# ext_esp32_M.net
KiCad netlist of a schematic drawn in EAGLE
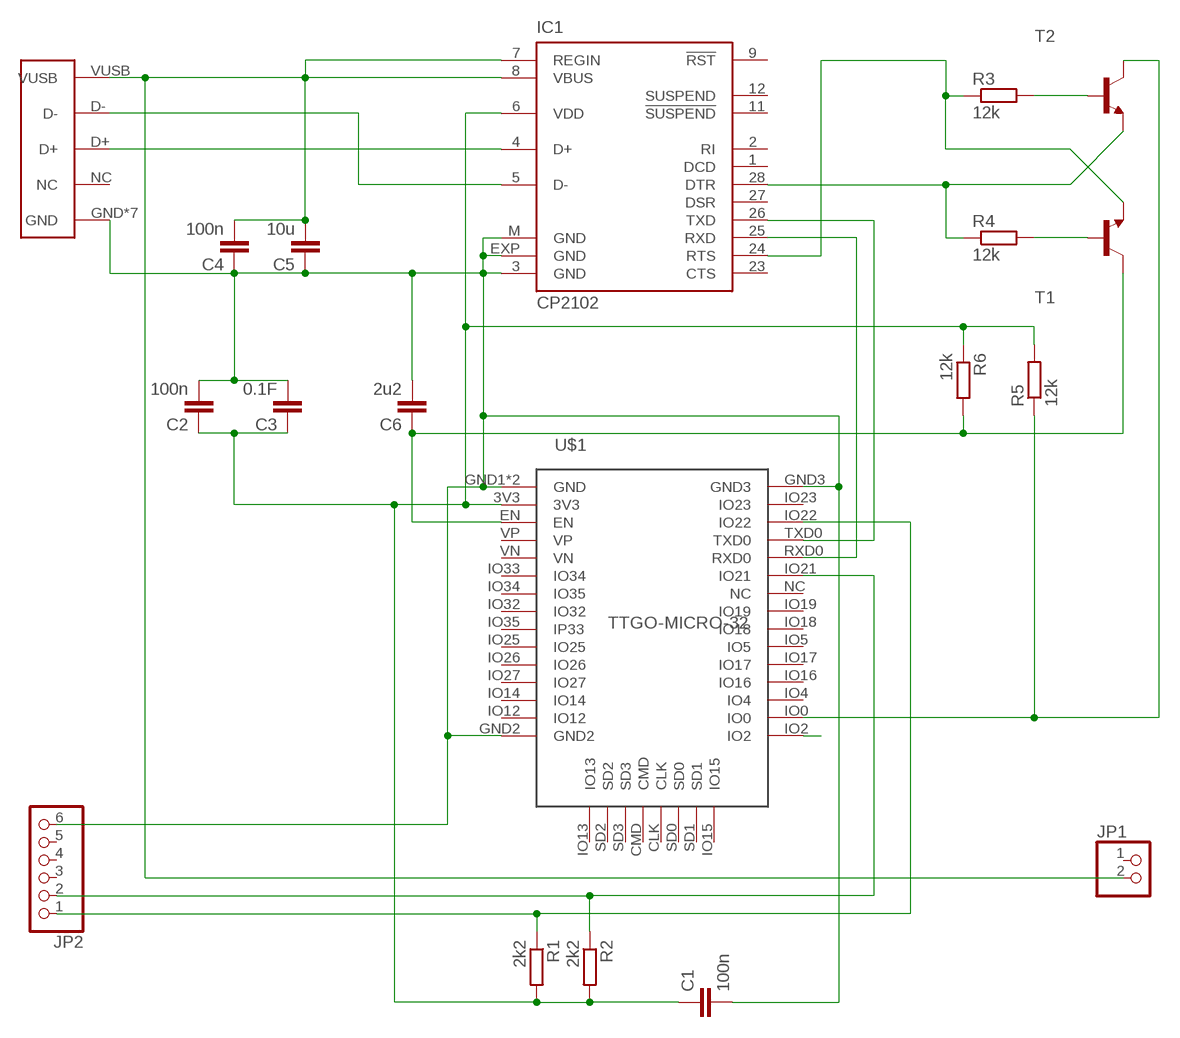
[diagram p0: schematic, sheet 1]

(export (version "E")
  (design (tool "Eeschema 10.0.6"))
  (components
    (comp (ref "C1")
      (value "100n")
      (footprint "eagle-import:C0603")
      (libsource (lib "eagle-import") (part "C-EUC0603"))
    )
    (comp (ref "C2")
      (value "100n")
      (footprint "eagle-import:C0603")
      (libsource (lib "eagle-import") (part "C-EUC0603"))
    )
    (comp (ref "C3")
      (value "0.1F")
      (footprint "eagle-import:C0603")
      (libsource (lib "eagle-import") (part "C-EUC0603"))
    )
    (comp (ref "C4")
      (value "100n")
      (footprint "eagle-import:C0603")
      (libsource (lib "eagle-import") (part "C-EUC0603"))
    )
    (comp (ref "C5")
      (value "10u")
      (footprint "eagle-import:C0603")
      (libsource (lib "eagle-import") (part "C-EUC0603"))
    )
    (comp (ref "C6")
      (value "2u2")
      (footprint "eagle-import:C0603")
      (libsource (lib "eagle-import") (part "C-EUC0603"))
    )
    (comp (ref "IC1")
      (value "CP2102")
      (footprint "eagle-import:MLP28")
      (fields (field (name "MF") "FARNELL") (field (name "MPN") "CP2102-GM"))
      (libsource (lib "eagle-import") (part "CP2102"))
    )
    (comp (ref "JP1")
      (value "PINHD-1X2")
      (footprint "eagle-import:1X02")
      (libsource (lib "eagle-import") (part "PINHD-1X2"))
    )
    (comp (ref "JP2")
      (value "PINHD-1X6")
      (footprint "eagle-import:1X06")
      (libsource (lib "eagle-import") (part "PINHD-1X6"))
    )
    (comp (ref "R1")
      (value "2k2")
      (footprint "eagle-import:R0603")
      (libsource (lib "eagle-import") (part "R-EU_R0603"))
    )
    (comp (ref "R2")
      (value "2k2")
      (footprint "eagle-import:R0603")
      (libsource (lib "eagle-import") (part "R-EU_R0603"))
    )
    (comp (ref "R3")
      (value "12k")
      (footprint "eagle-import:R0603")
      (libsource (lib "eagle-import") (part "R-EU_R0603"))
    )
    (comp (ref "R4")
      (value "12k")
      (footprint "eagle-import:R0603")
      (libsource (lib "eagle-import") (part "R-EU_R0603"))
    )
    (comp (ref "R5")
      (value "12k")
      (footprint "eagle-import:R0603")
      (libsource (lib "eagle-import") (part "R-EU_R0603"))
    )
    (comp (ref "R6")
      (value "12k")
      (footprint "eagle-import:R0603")
      (libsource (lib "eagle-import") (part "R-EU_R0603"))
    )
    (comp (ref "T1")
      (value "BC808-NPN-SOT23-BEC")
      (footprint "eagle-import:SOT23-BEC")
      (libsource (lib "eagle-import") (part "-NPN-SOT23-BECBC808"))
    )
    (comp (ref "T2")
      (value "BC808-NPN-SOT23-BEC")
      (footprint "eagle-import:SOT23-BEC")
      (libsource (lib "eagle-import") (part "-NPN-SOT23-BECBC808"))
    )
    (comp (ref "U$1")
      (value "TTGO-MICRO-32")
      (footprint "eagle-import:TTGO-MICRO-32")
      (libsource (lib "eagle-import") (part "TTGO-MICRO-32"))
    )
    (comp (ref "USB")
      (value "MICRO-USB")
      (footprint "eagle-import:MICRO-USB")
      (libsource (lib "eagle-import") (part "MICRO-USB"))
    )
  )
  (nets
    (net (code "1") (name "Net-(C1-Pad2)") (class "Default")
      (node (ref "C1") (pin "2") (pinfunction "2_2") (pintype "passive"))
      (node (ref "C2") (pin "2") (pinfunction "2_2") (pintype "passive"))
      (node (ref "C3") (pin "2") (pinfunction "2_2") (pintype "passive"))
      (node (ref "C4") (pin "1") (pinfunction "1_1") (pintype "passive"))
      (node (ref "C5") (pin "1") (pinfunction "1_1") (pintype "passive"))
      (node (ref "C6") (pin "2") (pinfunction "2_2") (pintype "passive"))
      (node (ref "IC1") (pin "3") (pinfunction "GND_3") (pintype "power_in"))
      (node (ref "IC1") (pin "EXP") (pinfunction "GND_EXP") (pintype "power_in"))
      (node (ref "IC1") (pin "M") (pinfunction "GND_M") (pintype "power_in"))
      (node (ref "JP2") (pin "6") (pinfunction "6_6") (pintype "passive"))
      (node (ref "U$1") (pin "GND1") (pinfunction "GND_GND1") (pintype "power_in"))
      (node (ref "U$1") (pin "GND2") (pinfunction "GND2_GND2") (pintype "power_in"))
      (node (ref "U$1") (pin "GND3") (pinfunction "GND3_GND3") (pintype "power_in"))
      (node (ref "U$1") (pin "GND4") (pinfunction "GND_GND4") (pintype "power_in"))
      (node (ref "USB") (pin "GND") (pinfunction "GND_GND") (pintype "bidirectional"))
      (node (ref "USB") (pin "GND1") (pinfunction "GND_GND1") (pintype "bidirectional"))
      (node (ref "USB") (pin "GND2") (pinfunction "GND_GND2") (pintype "bidirectional"))
      (node (ref "USB") (pin "GND3") (pinfunction "GND_GND3") (pintype "bidirectional"))
      (node (ref "USB") (pin "GND4") (pinfunction "GND_GND4") (pintype "bidirectional"))
      (node (ref "USB") (pin "P$1") (pinfunction "GND_P$1") (pintype "bidirectional"))
      (node (ref "USB") (pin "P$2") (pinfunction "GND_P$2") (pintype "bidirectional"))
    )
    (net (code "2") (name "Net-(C6-Pad1)") (class "Default")
      (node (ref "C6") (pin "1") (pinfunction "1_1") (pintype "passive"))
      (node (ref "R6") (pin "2") (pinfunction "2_2") (pintype "passive"))
      (node (ref "T1") (pin "C") (pinfunction "C_C") (pintype "passive"))
      (node (ref "U$1") (pin "EN") (pinfunction "EN_EN") (pintype "bidirectional"))
    )
    (net (code "3") (name "Net-(IC1-D+)") (class "Default")
      (node (ref "IC1") (pin "4") (pinfunction "D+_4") (pintype "bidirectional"))
      (node (ref "USB") (pin "D+") (pinfunction "D+_D+") (pintype "bidirectional"))
    )
    (net (code "4") (name "Net-(IC1-D-)") (class "Default")
      (node (ref "IC1") (pin "5") (pinfunction "D-_5") (pintype "bidirectional"))
      (node (ref "USB") (pin "D-") (pinfunction "D-_D-") (pintype "bidirectional"))
    )
    (net (code "5") (name "Net-(IC1-DTR)") (class "Default")
      (node (ref "IC1") (pin "28") (pinfunction "DTR_28") (pintype "output"))
      (node (ref "R4") (pin "1") (pinfunction "1_1") (pintype "passive"))
      (node (ref "T2") (pin "E") (pinfunction "E_E") (pintype "passive"))
    )
    (net (code "6") (name "Net-(IC1-REGIN)") (class "Default")
      (node (ref "C4") (pin "2") (pinfunction "2_2") (pintype "passive"))
      (node (ref "C5") (pin "2") (pinfunction "2_2") (pintype "passive"))
      (node (ref "IC1") (pin "7") (pinfunction "REGIN_7") (pintype "passive"))
      (node (ref "IC1") (pin "8") (pinfunction "VBUS_8") (pintype "input"))
      (node (ref "JP1") (pin "2") (pinfunction "2_2") (pintype "passive"))
      (node (ref "USB") (pin "VUSB") (pinfunction "VUSB_VUSB") (pintype "bidirectional"))
    )
    (net (code "7") (name "Net-(IC1-RTS)") (class "Default")
      (node (ref "IC1") (pin "24") (pinfunction "RTS_24") (pintype "output"))
      (node (ref "R3") (pin "1") (pinfunction "1_1") (pintype "passive"))
      (node (ref "T1") (pin "E") (pinfunction "E_E") (pintype "passive"))
    )
    (net (code "8") (name "Net-(IC1-RXD)") (class "Default")
      (node (ref "IC1") (pin "25") (pinfunction "RXD_25") (pintype "input"))
      (node (ref "U$1") (pin "RXD0") (pinfunction "RXD0_RXD0") (pintype "bidirectional"))
    )
    (net (code "9") (name "Net-(IC1-TXD)") (class "Default")
      (node (ref "IC1") (pin "26") (pinfunction "TXD_26") (pintype "output"))
      (node (ref "U$1") (pin "TXD0") (pinfunction "TXD0_TXD0") (pintype "bidirectional"))
    )
    (net (code "10") (name "Net-(IC1-VDD)") (class "Default")
      (node (ref "C1") (pin "1") (pinfunction "1_1") (pintype "passive"))
      (node (ref "C2") (pin "1") (pinfunction "1_1") (pintype "passive"))
      (node (ref "C3") (pin "1") (pinfunction "1_1") (pintype "passive"))
      (node (ref "IC1") (pin "6") (pinfunction "VDD_6") (pintype "power_in"))
      (node (ref "R1") (pin "2") (pinfunction "2_2") (pintype "passive"))
      (node (ref "R2") (pin "2") (pinfunction "2_2") (pintype "passive"))
      (node (ref "R5") (pin "2") (pinfunction "2_2") (pintype "passive"))
      (node (ref "R6") (pin "1") (pinfunction "1_1") (pintype "passive"))
      (node (ref "U$1") (pin "3V3") (pinfunction "3V3_3V3") (pintype "power_in"))
    )
    (net (code "11") (name "Net-(JP2-Pad1)") (class "Default")
      (node (ref "JP2") (pin "1") (pinfunction "1_1") (pintype "passive"))
      (node (ref "R1") (pin "1") (pinfunction "1_1") (pintype "passive"))
      (node (ref "U$1") (pin "IO22") (pinfunction "IO22_IO22") (pintype "bidirectional"))
    )
    (net (code "12") (name "Net-(JP2-Pad2)") (class "Default")
      (node (ref "JP2") (pin "2") (pinfunction "2_2") (pintype "passive"))
      (node (ref "R2") (pin "1") (pinfunction "1_1") (pintype "passive"))
      (node (ref "U$1") (pin "IO21") (pinfunction "IO21_IO21") (pintype "bidirectional"))
    )
    (net (code "13") (name "Net-(R3-Pad2)") (class "Default")
      (node (ref "R3") (pin "2") (pinfunction "2_2") (pintype "passive"))
      (node (ref "T2") (pin "B") (pinfunction "B_B") (pintype "passive"))
    )
    (net (code "14") (name "Net-(R4-Pad2)") (class "Default")
      (node (ref "R4") (pin "2") (pinfunction "2_2") (pintype "passive"))
      (node (ref "T1") (pin "B") (pinfunction "B_B") (pintype "passive"))
    )
    (net (code "15") (name "Net-(R5-Pad1)") (class "Default")
      (node (ref "R5") (pin "1") (pinfunction "1_1") (pintype "passive"))
      (node (ref "T2") (pin "C") (pinfunction "C_C") (pintype "passive"))
      (node (ref "U$1") (pin "IO0") (pinfunction "IO0_IO0") (pintype "bidirectional"))
    )
    (net (code "16") (name "unconnected-(IC1-CTS-Pad23)") (class "Default")
      (node (ref "IC1") (pin "23") (pinfunction "CTS_23") (pintype "input"))
    )
    (net (code "17") (name "unconnected-(IC1-DCD-Pad1)") (class "Default")
      (node (ref "IC1") (pin "1") (pinfunction "DCD_1") (pintype "input"))
    )
    (net (code "18") (name "unconnected-(IC1-DSR-Pad27)") (class "Default")
      (node (ref "IC1") (pin "27") (pinfunction "DSR_27") (pintype "input"))
    )
    (net (code "19") (name "unconnected-(IC1-RI-Pad2)") (class "Default")
      (node (ref "IC1") (pin "2") (pinfunction "RI_2") (pintype "input"))
    )
    (net (code "20") (name "unconnected-(IC1-SUSPEND-Pad12)") (class "Default")
      (node (ref "IC1") (pin "12") (pinfunction "SUSPEND_12") (pintype "output"))
    )
    (net (code "21") (name "unconnected-(IC1-~{RST}-Pad9)") (class "Default")
      (node (ref "IC1") (pin "9") (pinfunction "~{RST}_9") (pintype "bidirectional"))
    )
    (net (code "22") (name "unconnected-(IC1-~{SUSPEND}-Pad11)") (class "Default")
      (node (ref "IC1") (pin "11") (pinfunction "~{SUSPEND}_11") (pintype "output"))
    )
    (net (code "23") (name "unconnected-(JP1-Pad1)") (class "Default")
      (node (ref "JP1") (pin "1") (pinfunction "1_1") (pintype "passive"))
    )
    (net (code "24") (name "unconnected-(JP2-Pad3)") (class "Default")
      (node (ref "JP2") (pin "3") (pinfunction "3_3") (pintype "passive"))
    )
    (net (code "25") (name "unconnected-(JP2-Pad4)") (class "Default")
      (node (ref "JP2") (pin "4") (pinfunction "4_4") (pintype "passive"))
    )
    (net (code "26") (name "unconnected-(JP2-Pad5)") (class "Default")
      (node (ref "JP2") (pin "5") (pinfunction "5_5") (pintype "passive"))
    )
    (net (code "27") (name "unconnected-(U$1-IO34-PadIO33)") (class "Default")
      (node (ref "U$1") (pin "IO33") (pinfunction "IO34_IO33") (pintype "bidirectional"))
    )
    (net (code "28") (name "unconnected-(U$1-IO35-PadIO34)") (class "Default")
      (node (ref "U$1") (pin "IO34") (pinfunction "IO35_IO34") (pintype "bidirectional"))
    )
    (net (code "29") (name "unconnected-(U$1-IP33-PadIO35)") (class "Default")
      (node (ref "U$1") (pin "IO35") (pinfunction "IP33_IO35") (pintype "bidirectional"))
    )
    (net (code "30") (name "unconnected-(U$1-PadCLK)") (class "Default")
      (node (ref "U$1") (pin "CLK") (pinfunction "CLK_CLK") (pintype "bidirectional"))
    )
    (net (code "31") (name "unconnected-(U$1-PadCMD)") (class "Default")
      (node (ref "U$1") (pin "CMD") (pinfunction "CMD_CMD") (pintype "bidirectional"))
    )
    (net (code "32") (name "unconnected-(U$1-PadIO2)") (class "Default")
      (node (ref "U$1") (pin "IO2") (pinfunction "IO2_IO2") (pintype "bidirectional"))
    )
    (net (code "33") (name "unconnected-(U$1-PadIO4)") (class "Default")
      (node (ref "U$1") (pin "IO4") (pinfunction "IO4_IO4") (pintype "bidirectional"))
    )
    (net (code "34") (name "unconnected-(U$1-PadIO5)") (class "Default")
      (node (ref "U$1") (pin "IO5") (pinfunction "IO5_IO5") (pintype "bidirectional"))
    )
    (net (code "35") (name "unconnected-(U$1-PadIO12)") (class "Default")
      (node (ref "U$1") (pin "IO12") (pinfunction "IO12_IO12") (pintype "bidirectional"))
    )
    (net (code "36") (name "unconnected-(U$1-PadIO13)") (class "Default")
      (node (ref "U$1") (pin "IO13") (pinfunction "IO13_IO13") (pintype "bidirectional"))
    )
    (net (code "37") (name "unconnected-(U$1-PadIO14)") (class "Default")
      (node (ref "U$1") (pin "IO14") (pinfunction "IO14_IO14") (pintype "bidirectional"))
    )
    (net (code "38") (name "unconnected-(U$1-PadIO15)") (class "Default")
      (node (ref "U$1") (pin "IO15") (pinfunction "IO15_IO15") (pintype "bidirectional"))
    )
    (net (code "39") (name "unconnected-(U$1-PadIO16)") (class "Default")
      (node (ref "U$1") (pin "IO16") (pinfunction "IO16_IO16") (pintype "bidirectional"))
    )
    (net (code "40") (name "unconnected-(U$1-PadIO17)") (class "Default")
      (node (ref "U$1") (pin "IO17") (pinfunction "IO17_IO17") (pintype "bidirectional"))
    )
    (net (code "41") (name "unconnected-(U$1-PadIO18)") (class "Default")
      (node (ref "U$1") (pin "IO18") (pinfunction "IO18_IO18") (pintype "bidirectional"))
    )
    (net (code "42") (name "unconnected-(U$1-PadIO19)") (class "Default")
      (node (ref "U$1") (pin "IO19") (pinfunction "IO19_IO19") (pintype "bidirectional"))
    )
    (net (code "43") (name "unconnected-(U$1-PadIO23)") (class "Default")
      (node (ref "U$1") (pin "IO23") (pinfunction "IO23_IO23") (pintype "bidirectional"))
    )
    (net (code "44") (name "unconnected-(U$1-PadIO25)") (class "Default")
      (node (ref "U$1") (pin "IO25") (pinfunction "IO25_IO25") (pintype "bidirectional"))
    )
    (net (code "45") (name "unconnected-(U$1-PadIO26)") (class "Default")
      (node (ref "U$1") (pin "IO26") (pinfunction "IO26_IO26") (pintype "bidirectional"))
    )
    (net (code "46") (name "unconnected-(U$1-PadIO27)") (class "Default")
      (node (ref "U$1") (pin "IO27") (pinfunction "IO27_IO27") (pintype "bidirectional"))
    )
    (net (code "47") (name "unconnected-(U$1-PadIO32)") (class "Default")
      (node (ref "U$1") (pin "IO32") (pinfunction "IO32_IO32") (pintype "bidirectional"))
    )
    (net (code "48") (name "unconnected-(U$1-PadNC)") (class "Default")
      (node (ref "U$1") (pin "NC") (pinfunction "NC_NC") (pintype "no_connect"))
    )
    (net (code "49") (name "unconnected-(U$1-PadSD0)") (class "Default")
      (node (ref "U$1") (pin "SD0") (pinfunction "SD0_SD0") (pintype "bidirectional"))
    )
    (net (code "50") (name "unconnected-(U$1-PadSD1)") (class "Default")
      (node (ref "U$1") (pin "SD1") (pinfunction "SD1_SD1") (pintype "bidirectional"))
    )
    (net (code "51") (name "unconnected-(U$1-PadSD2)") (class "Default")
      (node (ref "U$1") (pin "SD2") (pinfunction "SD2_SD2") (pintype "bidirectional"))
    )
    (net (code "52") (name "unconnected-(U$1-PadSD3)") (class "Default")
      (node (ref "U$1") (pin "SD3") (pinfunction "SD3_SD3") (pintype "bidirectional"))
    )
    (net (code "53") (name "unconnected-(U$1-PadVN)") (class "Default")
      (node (ref "U$1") (pin "VN") (pinfunction "VN_VN") (pintype "bidirectional"))
    )
    (net (code "54") (name "unconnected-(U$1-PadVP)") (class "Default")
      (node (ref "U$1") (pin "VP") (pinfunction "VP_VP") (pintype "bidirectional"))
    )
    (net (code "55") (name "unconnected-(USB-PadNC)") (class "Default")
      (node (ref "USB") (pin "NC") (pinfunction "NC_NC") (pintype "bidirectional"))
    )
  )
)
